# Ports.net
KiCad netlist of a schematic drawn in Altium Designer
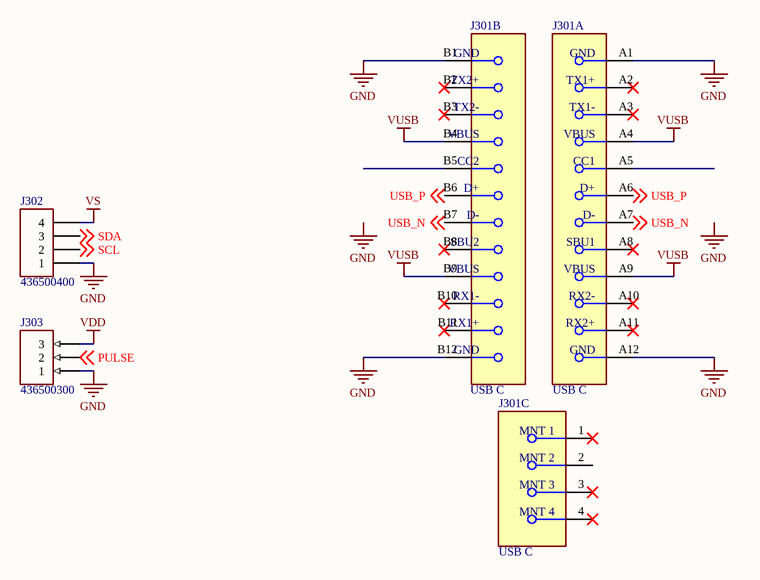
[diagram p0: Ports.SchDoc]

(export (version "E")
  (design (tool "Eeschema 10.0.6"))
  (components
    (comp (ref "J301")
      (value "USB C")
      (footprint "FP-1054500101-MFG")
      (description "CONN RCP USB3.1 TYPEC 24P SMD RA")
      (fields
        (field (name "MANUFACTURER") "Molex")
        (field (name "OCTOPART") "https://octopart.com/105450-0101-molex-68082325")
      )
      (libsource (lib "") (part "1054500101_1"))
    )
    (comp (ref "J302")
      (value "436500400")
      (footprint "436500400")
      (libsource (lib "Main") (part "436500400"))
    )
    (comp (ref "J303")
      (value "436500300")
      (footprint "436500300")
      (libsource (lib "Main") (part "436500300"))
    )
  )
  (nets
    (net (code "1") (name "GND") (class "Default")
      (node (ref "J301") (pin "A1") (pinfunction "GND_A1") (pintype "passive"))
      (node (ref "J301") (pin "A12") (pinfunction "GND_A12") (pintype "passive"))
      (node (ref "J301") (pin "B1") (pinfunction "GND_B1") (pintype "passive"))
      (node (ref "J301") (pin "B12") (pinfunction "GND_B12") (pintype "passive"))
      (node (ref "J302") (pin "1") (pinfunction "1_1") (pintype "passive"))
      (node (ref "J303") (pin "1") (pinfunction "1_1") (pintype "input"))
    )
    (net (code "2") (name "PULSE") (class "Default")
      (node (ref "J303") (pin "2") (pinfunction "2_2") (pintype "input"))
    )
    (net (code "3") (name "SCL") (class "Default")
      (node (ref "J302") (pin "2") (pinfunction "2_2") (pintype "passive"))
    )
    (net (code "4") (name "SDA") (class "Default")
      (node (ref "J302") (pin "3") (pinfunction "3_3") (pintype "passive"))
    )
    (net (code "5") (name "USB_N") (class "Default")
      (node (ref "J301") (pin "A7") (pinfunction "D-_A7") (pintype "passive"))
      (node (ref "J301") (pin "B7") (pinfunction "D-_B7") (pintype "passive"))
    )
    (net (code "6") (name "USB_P") (class "Default")
      (node (ref "J301") (pin "A6") (pinfunction "D+_A6") (pintype "passive"))
      (node (ref "J301") (pin "B6") (pinfunction "D+_B6") (pintype "passive"))
    )
    (net (code "7") (name "VDD") (class "Default")
      (node (ref "J303") (pin "3") (pinfunction "3_3") (pintype "input"))
    )
    (net (code "8") (name "VS") (class "Default")
      (node (ref "J302") (pin "4") (pinfunction "4_4") (pintype "passive"))
    )
    (net (code "9") (name "VUSB") (class "Default")
      (node (ref "J301") (pin "A4") (pinfunction "VBUS_A4") (pintype "passive"))
      (node (ref "J301") (pin "A9") (pinfunction "VBUS_A9") (pintype "passive"))
      (node (ref "J301") (pin "B4") (pinfunction "VBUS_B4") (pintype "passive"))
      (node (ref "J301") (pin "B9") (pinfunction "VBUS_B9") (pintype "passive"))
    )
    (net (code "10") (name "unconnected-(J301A-CC1-PadA5)") (class "Default")
      (node (ref "J301") (pin "A5") (pinfunction "CC1_A5") (pintype "passive"))
    )
    (net (code "11") (name "unconnected-(J301A-RX2+-PadA11)") (class "Default")
      (node (ref "J301") (pin "A11") (pinfunction "RX2+_A11") (pintype "passive+no_connect"))
    )
    (net (code "12") (name "unconnected-(J301A-RX2--PadA10)") (class "Default")
      (node (ref "J301") (pin "A10") (pinfunction "RX2-_A10") (pintype "passive+no_connect"))
    )
    (net (code "13") (name "unconnected-(J301A-SBU1-PadA8)") (class "Default")
      (node (ref "J301") (pin "A8") (pinfunction "SBU1_A8") (pintype "passive+no_connect"))
    )
    (net (code "14") (name "unconnected-(J301A-TX1+-PadA2)") (class "Default")
      (node (ref "J301") (pin "A2") (pinfunction "TX1+_A2") (pintype "passive+no_connect"))
    )
    (net (code "15") (name "unconnected-(J301A-TX1--PadA3)") (class "Default")
      (node (ref "J301") (pin "A3") (pinfunction "TX1-_A3") (pintype "passive+no_connect"))
    )
    (net (code "16") (name "unconnected-(J301B-CC2-PadB5)") (class "Default")
      (node (ref "J301") (pin "B5") (pinfunction "CC2_B5") (pintype "passive"))
    )
    (net (code "17") (name "unconnected-(J301B-RX1+-PadB11)") (class "Default")
      (node (ref "J301") (pin "B11") (pinfunction "RX1+_B11") (pintype "passive+no_connect"))
    )
    (net (code "18") (name "unconnected-(J301B-RX1--PadB10)") (class "Default")
      (node (ref "J301") (pin "B10") (pinfunction "RX1-_B10") (pintype "passive+no_connect"))
    )
    (net (code "19") (name "unconnected-(J301B-SBU2-PadB8)") (class "Default")
      (node (ref "J301") (pin "B8") (pinfunction "SBU2_B8") (pintype "passive+no_connect"))
    )
    (net (code "20") (name "unconnected-(J301B-TX2+-PadB2)") (class "Default")
      (node (ref "J301") (pin "B2") (pinfunction "TX2+_B2") (pintype "passive+no_connect"))
    )
    (net (code "21") (name "unconnected-(J301B-TX2--PadB3)") (class "Default")
      (node (ref "J301") (pin "B3") (pinfunction "TX2-_B3") (pintype "passive+no_connect"))
    )
    (net (code "22") (name "unconnected-(J301C-MNT_1-Pad1)") (class "Default")
      (node (ref "J301") (pin "1") (pinfunction "MNT_1_1") (pintype "passive+no_connect"))
    )
    (net (code "23") (name "unconnected-(J301C-MNT_2-Pad2)") (class "Default")
      (node (ref "J301") (pin "2") (pinfunction "MNT_2_2") (pintype "passive"))
    )
    (net (code "24") (name "unconnected-(J301C-MNT_3-Pad3)") (class "Default")
      (node (ref "J301") (pin "3") (pinfunction "MNT_3_3") (pintype "passive+no_connect"))
    )
    (net (code "25") (name "unconnected-(J301C-MNT_4-Pad4)") (class "Default")
      (node (ref "J301") (pin "4") (pinfunction "MNT_4_4") (pintype "passive+no_connect"))
    )
  )
)
